# led_reflector.net
KiCad netlist of a schematic drawn in EAGLE
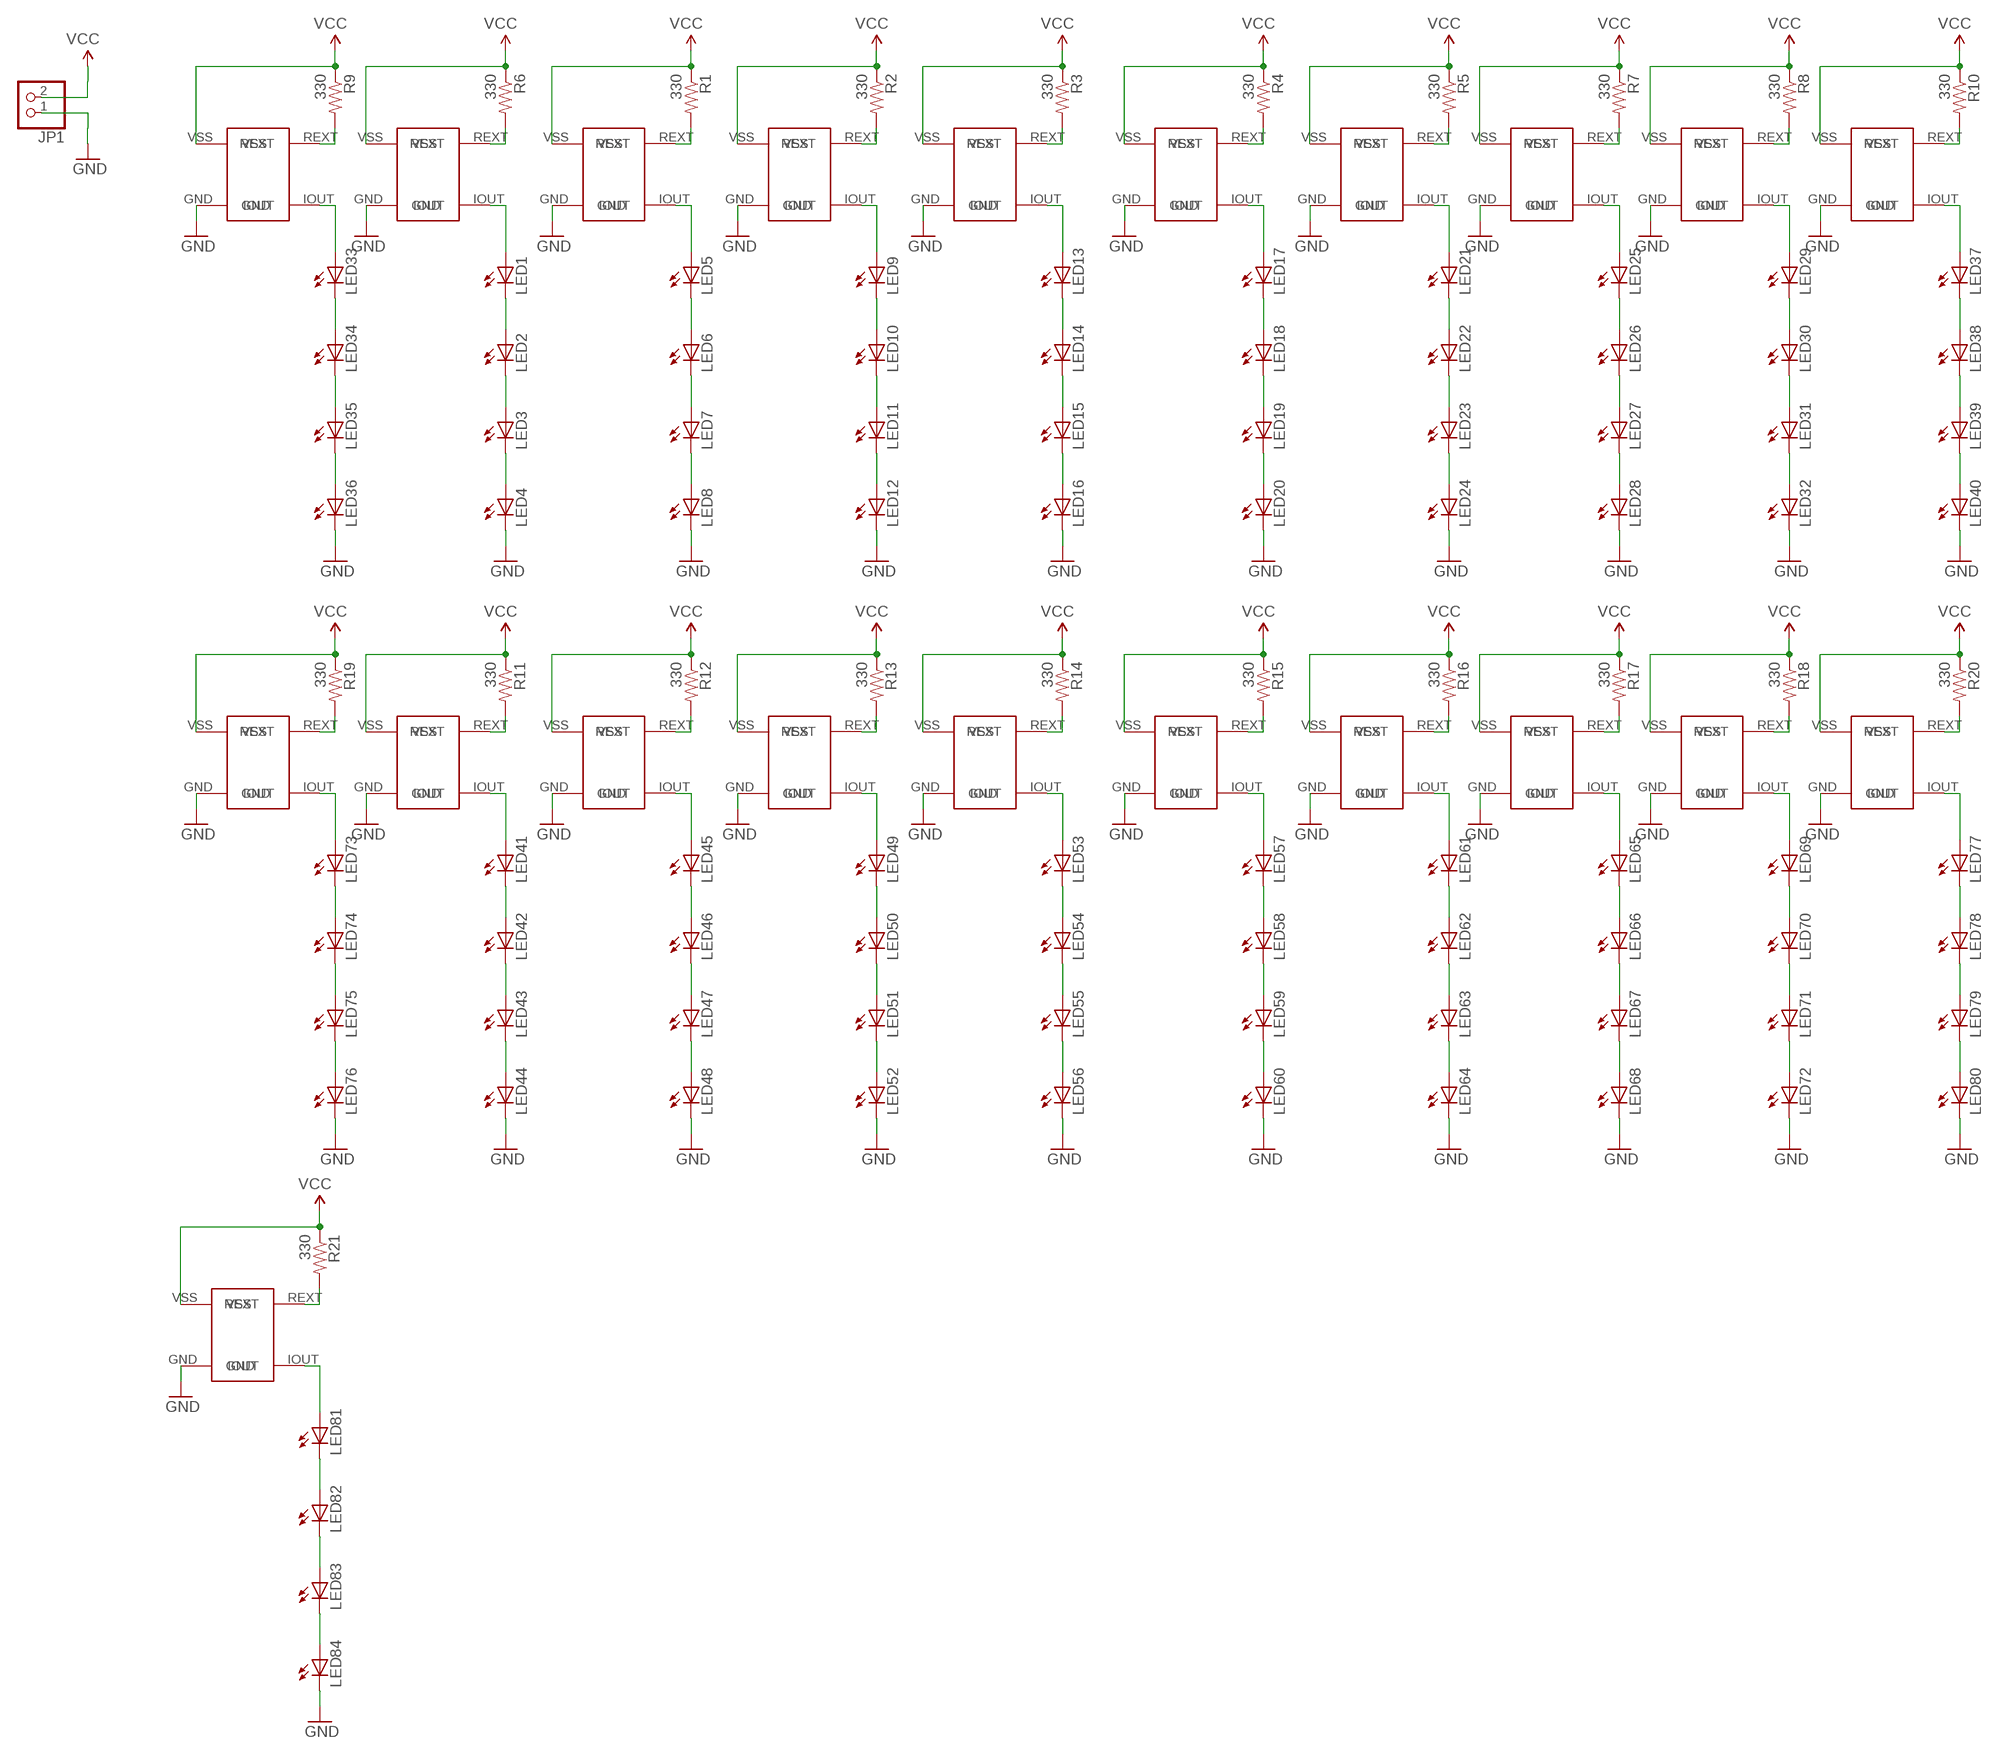
[diagram p0: schematic, sheet 1]

(export (version "E")
  (design (tool "Eeschema 10.0.6"))
  (components
    (comp (ref "JP1")
      (value "PINHD-1X2")
      (footprint "eagle-import:1X02")
      (libsource (lib "eagle-import") (part "PINHD-1X2"))
    )
    (comp (ref "LED1")
      (value "LED5MM")
      (footprint "eagle-import:LED5MM")
      (libsource (lib "eagle-import") (part "LED5MM"))
    )
    (comp (ref "LED2")
      (value "LED5MM")
      (footprint "eagle-import:LED5MM")
      (libsource (lib "eagle-import") (part "LED5MM"))
    )
    (comp (ref "LED3")
      (value "LED5MM")
      (footprint "eagle-import:LED5MM")
      (libsource (lib "eagle-import") (part "LED5MM"))
    )
    (comp (ref "LED4")
      (value "LED5MM")
      (footprint "eagle-import:LED5MM")
      (libsource (lib "eagle-import") (part "LED5MM"))
    )
    (comp (ref "LED5")
      (value "LED5MM")
      (footprint "eagle-import:LED5MM")
      (libsource (lib "eagle-import") (part "LED5MM"))
    )
    (comp (ref "LED6")
      (value "LED5MM")
      (footprint "eagle-import:LED5MM")
      (libsource (lib "eagle-import") (part "LED5MM"))
    )
    (comp (ref "LED7")
      (value "LED5MM")
      (footprint "eagle-import:LED5MM")
      (libsource (lib "eagle-import") (part "LED5MM"))
    )
    (comp (ref "LED8")
      (value "LED5MM")
      (footprint "eagle-import:LED5MM")
      (libsource (lib "eagle-import") (part "LED5MM"))
    )
    (comp (ref "LED9")
      (value "LED5MM")
      (footprint "eagle-import:LED5MM")
      (libsource (lib "eagle-import") (part "LED5MM"))
    )
    (comp (ref "LED10")
      (value "LED5MM")
      (footprint "eagle-import:LED5MM")
      (libsource (lib "eagle-import") (part "LED5MM"))
    )
    (comp (ref "LED11")
      (value "LED5MM")
      (footprint "eagle-import:LED5MM")
      (libsource (lib "eagle-import") (part "LED5MM"))
    )
    (comp (ref "LED12")
      (value "LED5MM")
      (footprint "eagle-import:LED5MM")
      (libsource (lib "eagle-import") (part "LED5MM"))
    )
    (comp (ref "LED13")
      (value "LED5MM")
      (footprint "eagle-import:LED5MM")
      (libsource (lib "eagle-import") (part "LED5MM"))
    )
    (comp (ref "LED14")
      (value "LED5MM")
      (footprint "eagle-import:LED5MM")
      (libsource (lib "eagle-import") (part "LED5MM"))
    )
    (comp (ref "LED15")
      (value "LED5MM")
      (footprint "eagle-import:LED5MM")
      (libsource (lib "eagle-import") (part "LED5MM"))
    )
    (comp (ref "LED16")
      (value "LED5MM")
      (footprint "eagle-import:LED5MM")
      (libsource (lib "eagle-import") (part "LED5MM"))
    )
    (comp (ref "LED17")
      (value "LED5MM")
      (footprint "eagle-import:LED5MM")
      (libsource (lib "eagle-import") (part "LED5MM"))
    )
    (comp (ref "LED18")
      (value "LED5MM")
      (footprint "eagle-import:LED5MM")
      (libsource (lib "eagle-import") (part "LED5MM"))
    )
    (comp (ref "LED19")
      (value "LED5MM")
      (footprint "eagle-import:LED5MM")
      (libsource (lib "eagle-import") (part "LED5MM"))
    )
    (comp (ref "LED20")
      (value "LED5MM")
      (footprint "eagle-import:LED5MM")
      (libsource (lib "eagle-import") (part "LED5MM"))
    )
    (comp (ref "LED21")
      (value "LED5MM")
      (footprint "eagle-import:LED5MM")
      (libsource (lib "eagle-import") (part "LED5MM"))
    )
    (comp (ref "LED22")
      (value "LED5MM")
      (footprint "eagle-import:LED5MM")
      (libsource (lib "eagle-import") (part "LED5MM"))
    )
    (comp (ref "LED23")
      (value "LED5MM")
      (footprint "eagle-import:LED5MM")
      (libsource (lib "eagle-import") (part "LED5MM"))
    )
    (comp (ref "LED24")
      (value "LED5MM")
      (footprint "eagle-import:LED5MM")
      (libsource (lib "eagle-import") (part "LED5MM"))
    )
    (comp (ref "LED25")
      (value "LED5MM")
      (footprint "eagle-import:LED5MM")
      (libsource (lib "eagle-import") (part "LED5MM"))
    )
    (comp (ref "LED26")
      (value "LED5MM")
      (footprint "eagle-import:LED5MM")
      (libsource (lib "eagle-import") (part "LED5MM"))
    )
    (comp (ref "LED27")
      (value "LED5MM")
      (footprint "eagle-import:LED5MM")
      (libsource (lib "eagle-import") (part "LED5MM"))
    )
    (comp (ref "LED28")
      (value "LED5MM")
      (footprint "eagle-import:LED5MM")
      (libsource (lib "eagle-import") (part "LED5MM"))
    )
    (comp (ref "LED29")
      (value "LED5MM")
      (footprint "eagle-import:LED5MM")
      (libsource (lib "eagle-import") (part "LED5MM"))
    )
    (comp (ref "LED30")
      (value "LED5MM")
      (footprint "eagle-import:LED5MM")
      (libsource (lib "eagle-import") (part "LED5MM"))
    )
    (comp (ref "LED31")
      (value "LED5MM")
      (footprint "eagle-import:LED5MM")
      (libsource (lib "eagle-import") (part "LED5MM"))
    )
    (comp (ref "LED32")
      (value "LED5MM")
      (footprint "eagle-import:LED5MM")
      (libsource (lib "eagle-import") (part "LED5MM"))
    )
    (comp (ref "LED33")
      (value "LED5MM")
      (footprint "eagle-import:LED5MM")
      (libsource (lib "eagle-import") (part "LED5MM"))
    )
    (comp (ref "LED34")
      (value "LED5MM")
      (footprint "eagle-import:LED5MM")
      (libsource (lib "eagle-import") (part "LED5MM"))
    )
    (comp (ref "LED35")
      (value "LED5MM")
      (footprint "eagle-import:LED5MM")
      (libsource (lib "eagle-import") (part "LED5MM"))
    )
    (comp (ref "LED36")
      (value "LED5MM")
      (footprint "eagle-import:LED5MM")
      (libsource (lib "eagle-import") (part "LED5MM"))
    )
    (comp (ref "LED37")
      (value "LED5MM")
      (footprint "eagle-import:LED5MM")
      (libsource (lib "eagle-import") (part "LED5MM"))
    )
    (comp (ref "LED38")
      (value "LED5MM")
      (footprint "eagle-import:LED5MM")
      (libsource (lib "eagle-import") (part "LED5MM"))
    )
    (comp (ref "LED39")
      (value "LED5MM")
      (footprint "eagle-import:LED5MM")
      (libsource (lib "eagle-import") (part "LED5MM"))
    )
    (comp (ref "LED40")
      (value "LED5MM")
      (footprint "eagle-import:LED5MM")
      (libsource (lib "eagle-import") (part "LED5MM"))
    )
    (comp (ref "LED41")
      (value "LED5MM")
      (footprint "eagle-import:LED5MM")
      (libsource (lib "eagle-import") (part "LED5MM"))
    )
    (comp (ref "LED42")
      (value "LED5MM")
      (footprint "eagle-import:LED5MM")
      (libsource (lib "eagle-import") (part "LED5MM"))
    )
    (comp (ref "LED43")
      (value "LED5MM")
      (footprint "eagle-import:LED5MM")
      (libsource (lib "eagle-import") (part "LED5MM"))
    )
    (comp (ref "LED44")
      (value "LED5MM")
      (footprint "eagle-import:LED5MM")
      (libsource (lib "eagle-import") (part "LED5MM"))
    )
    (comp (ref "LED45")
      (value "LED5MM")
      (footprint "eagle-import:LED5MM")
      (libsource (lib "eagle-import") (part "LED5MM"))
    )
    (comp (ref "LED46")
      (value "LED5MM")
      (footprint "eagle-import:LED5MM")
      (libsource (lib "eagle-import") (part "LED5MM"))
    )
    (comp (ref "LED47")
      (value "LED5MM")
      (footprint "eagle-import:LED5MM")
      (libsource (lib "eagle-import") (part "LED5MM"))
    )
    (comp (ref "LED48")
      (value "LED5MM")
      (footprint "eagle-import:LED5MM")
      (libsource (lib "eagle-import") (part "LED5MM"))
    )
    (comp (ref "LED49")
      (value "LED5MM")
      (footprint "eagle-import:LED5MM")
      (libsource (lib "eagle-import") (part "LED5MM"))
    )
    (comp (ref "LED50")
      (value "LED5MM")
      (footprint "eagle-import:LED5MM")
      (libsource (lib "eagle-import") (part "LED5MM"))
    )
    (comp (ref "LED51")
      (value "LED5MM")
      (footprint "eagle-import:LED5MM")
      (libsource (lib "eagle-import") (part "LED5MM"))
    )
    (comp (ref "LED52")
      (value "LED5MM")
      (footprint "eagle-import:LED5MM")
      (libsource (lib "eagle-import") (part "LED5MM"))
    )
    (comp (ref "LED53")
      (value "LED5MM")
      (footprint "eagle-import:LED5MM")
      (libsource (lib "eagle-import") (part "LED5MM"))
    )
    (comp (ref "LED54")
      (value "LED5MM")
      (footprint "eagle-import:LED5MM")
      (libsource (lib "eagle-import") (part "LED5MM"))
    )
    (comp (ref "LED55")
      (value "LED5MM")
      (footprint "eagle-import:LED5MM")
      (libsource (lib "eagle-import") (part "LED5MM"))
    )
    (comp (ref "LED56")
      (value "LED5MM")
      (footprint "eagle-import:LED5MM")
      (libsource (lib "eagle-import") (part "LED5MM"))
    )
    (comp (ref "LED57")
      (value "LED5MM")
      (footprint "eagle-import:LED5MM")
      (libsource (lib "eagle-import") (part "LED5MM"))
    )
    (comp (ref "LED58")
      (value "LED5MM")
      (footprint "eagle-import:LED5MM")
      (libsource (lib "eagle-import") (part "LED5MM"))
    )
    (comp (ref "LED59")
      (value "LED5MM")
      (footprint "eagle-import:LED5MM")
      (libsource (lib "eagle-import") (part "LED5MM"))
    )
    (comp (ref "LED60")
      (value "LED5MM")
      (footprint "eagle-import:LED5MM")
      (libsource (lib "eagle-import") (part "LED5MM"))
    )
    (comp (ref "LED61")
      (value "LED5MM")
      (footprint "eagle-import:LED5MM")
      (libsource (lib "eagle-import") (part "LED5MM"))
    )
    (comp (ref "LED62")
      (value "LED5MM")
      (footprint "eagle-import:LED5MM")
      (libsource (lib "eagle-import") (part "LED5MM"))
    )
    (comp (ref "LED63")
      (value "LED5MM")
      (footprint "eagle-import:LED5MM")
      (libsource (lib "eagle-import") (part "LED5MM"))
    )
    (comp (ref "LED64")
      (value "LED5MM")
      (footprint "eagle-import:LED5MM")
      (libsource (lib "eagle-import") (part "LED5MM"))
    )
    (comp (ref "LED65")
      (value "LED5MM")
      (footprint "eagle-import:LED5MM")
      (libsource (lib "eagle-import") (part "LED5MM"))
    )
    (comp (ref "LED66")
      (value "LED5MM")
      (footprint "eagle-import:LED5MM")
      (libsource (lib "eagle-import") (part "LED5MM"))
    )
    (comp (ref "LED67")
      (value "LED5MM")
      (footprint "eagle-import:LED5MM")
      (libsource (lib "eagle-import") (part "LED5MM"))
    )
    (comp (ref "LED68")
      (value "LED5MM")
      (footprint "eagle-import:LED5MM")
      (libsource (lib "eagle-import") (part "LED5MM"))
    )
    (comp (ref "LED69")
      (value "LED5MM")
      (footprint "eagle-import:LED5MM")
      (libsource (lib "eagle-import") (part "LED5MM"))
    )
    (comp (ref "LED70")
      (value "LED5MM")
      (footprint "eagle-import:LED5MM")
      (libsource (lib "eagle-import") (part "LED5MM"))
    )
    (comp (ref "LED71")
      (value "LED5MM")
      (footprint "eagle-import:LED5MM")
      (libsource (lib "eagle-import") (part "LED5MM"))
    )
    (comp (ref "LED72")
      (value "LED5MM")
      (footprint "eagle-import:LED5MM")
      (libsource (lib "eagle-import") (part "LED5MM"))
    )
    (comp (ref "LED73")
      (value "LED5MM")
      (footprint "eagle-import:LED5MM")
      (libsource (lib "eagle-import") (part "LED5MM"))
    )
    (comp (ref "LED74")
      (value "LED5MM")
      (footprint "eagle-import:LED5MM")
      (libsource (lib "eagle-import") (part "LED5MM"))
    )
    (comp (ref "LED75")
      (value "LED5MM")
      (footprint "eagle-import:LED5MM")
      (libsource (lib "eagle-import") (part "LED5MM"))
    )
    (comp (ref "LED76")
      (value "LED5MM")
      (footprint "eagle-import:LED5MM")
      (libsource (lib "eagle-import") (part "LED5MM"))
    )
    (comp (ref "LED77")
      (value "LED5MM")
      (footprint "eagle-import:LED5MM")
      (libsource (lib "eagle-import") (part "LED5MM"))
    )
    (comp (ref "LED78")
      (value "LED5MM")
      (footprint "eagle-import:LED5MM")
      (libsource (lib "eagle-import") (part "LED5MM"))
    )
    (comp (ref "LED79")
      (value "LED5MM")
      (footprint "eagle-import:LED5MM")
      (libsource (lib "eagle-import") (part "LED5MM"))
    )
    (comp (ref "LED80")
      (value "LED5MM")
      (footprint "eagle-import:LED5MM")
      (libsource (lib "eagle-import") (part "LED5MM"))
    )
    (comp (ref "LED81")
      (value "LED5MM")
      (footprint "eagle-import:LED5MM")
      (libsource (lib "eagle-import") (part "LED5MM"))
    )
    (comp (ref "LED82")
      (value "LED5MM")
      (footprint "eagle-import:LED5MM")
      (libsource (lib "eagle-import") (part "LED5MM"))
    )
    (comp (ref "LED83")
      (value "LED5MM")
      (footprint "eagle-import:LED5MM")
      (libsource (lib "eagle-import") (part "LED5MM"))
    )
    (comp (ref "LED84")
      (value "LED5MM")
      (footprint "eagle-import:LED5MM")
      (libsource (lib "eagle-import") (part "LED5MM"))
    )
    (comp (ref "R1")
      (value "330")
      (footprint "eagle-import:0805")
      (libsource (lib "eagle-import") (part "RESISTOR"))
    )
    (comp (ref "R2")
      (value "330")
      (footprint "eagle-import:0805")
      (libsource (lib "eagle-import") (part "RESISTOR"))
    )
    (comp (ref "R3")
      (value "330")
      (footprint "eagle-import:0805")
      (libsource (lib "eagle-import") (part "RESISTOR"))
    )
    (comp (ref "R4")
      (value "330")
      (footprint "eagle-import:0805")
      (libsource (lib "eagle-import") (part "RESISTOR"))
    )
    (comp (ref "R5")
      (value "330")
      (footprint "eagle-import:0805")
      (libsource (lib "eagle-import") (part "RESISTOR"))
    )
    (comp (ref "R6")
      (value "330")
      (footprint "eagle-import:0805")
      (libsource (lib "eagle-import") (part "RESISTOR"))
    )
    (comp (ref "R7")
      (value "330")
      (footprint "eagle-import:0805")
      (libsource (lib "eagle-import") (part "RESISTOR"))
    )
    (comp (ref "R8")
      (value "330")
      (footprint "eagle-import:0805")
      (libsource (lib "eagle-import") (part "RESISTOR"))
    )
    (comp (ref "R9")
      (value "330")
      (footprint "eagle-import:0805")
      (libsource (lib "eagle-import") (part "RESISTOR"))
    )
    (comp (ref "R10")
      (value "330")
      (footprint "eagle-import:0805")
      (libsource (lib "eagle-import") (part "RESISTOR"))
    )
    (comp (ref "R11")
      (value "330")
      (footprint "eagle-import:0805")
      (libsource (lib "eagle-import") (part "RESISTOR"))
    )
    (comp (ref "R12")
      (value "330")
      (footprint "eagle-import:0805")
      (libsource (lib "eagle-import") (part "RESISTOR"))
    )
    (comp (ref "R13")
      (value "330")
      (footprint "eagle-import:0805")
      (libsource (lib "eagle-import") (part "RESISTOR"))
    )
    (comp (ref "R14")
      (value "330")
      (footprint "eagle-import:0805")
      (libsource (lib "eagle-import") (part "RESISTOR"))
    )
    (comp (ref "R15")
      (value "330")
      (footprint "eagle-import:0805")
      (libsource (lib "eagle-import") (part "RESISTOR"))
    )
    (comp (ref "R16")
      (value "330")
      (footprint "eagle-import:0805")
      (libsource (lib "eagle-import") (part "RESISTOR"))
    )
    (comp (ref "R17")
      (value "330")
      (footprint "eagle-import:0805")
      (libsource (lib "eagle-import") (part "RESISTOR"))
    )
    (comp (ref "R18")
      (value "330")
      (footprint "eagle-import:0805")
      (libsource (lib "eagle-import") (part "RESISTOR"))
    )
    (comp (ref "R19")
      (value "330")
      (footprint "eagle-import:0805")
      (libsource (lib "eagle-import") (part "RESISTOR"))
    )
    (comp (ref "R20")
      (value "330")
      (footprint "eagle-import:0805")
      (libsource (lib "eagle-import") (part "RESISTOR"))
    )
    (comp (ref "R21")
      (value "330")
      (footprint "eagle-import:0805")
      (libsource (lib "eagle-import") (part "RESISTOR"))
    )
    (comp (ref "U$1")
      (value "BCR401W")
      (footprint "eagle-import:SOT-343")
      (libsource (lib "eagle-import") (part "BCR401W"))
    )
    (comp (ref "U$2")
      (value "BCR401W")
      (footprint "eagle-import:SOT-343")
      (libsource (lib "eagle-import") (part "BCR401W"))
    )
    (comp (ref "U$3")
      (value "BCR401W")
      (footprint "eagle-import:SOT-343")
      (libsource (lib "eagle-import") (part "BCR401W"))
    )
    (comp (ref "U$4")
      (value "BCR401W")
      (footprint "eagle-import:SOT-343")
      (libsource (lib "eagle-import") (part "BCR401W"))
    )
    (comp (ref "U$5")
      (value "BCR401W")
      (footprint "eagle-import:SOT-343")
      (libsource (lib "eagle-import") (part "BCR401W"))
    )
    (comp (ref "U$6")
      (value "BCR401W")
      (footprint "eagle-import:SOT-343")
      (libsource (lib "eagle-import") (part "BCR401W"))
    )
    (comp (ref "U$7")
      (value "BCR401W")
      (footprint "eagle-import:SOT-343")
      (libsource (lib "eagle-import") (part "BCR401W"))
    )
    (comp (ref "U$8")
      (value "BCR401W")
      (footprint "eagle-import:SOT-343")
      (libsource (lib "eagle-import") (part "BCR401W"))
    )
    (comp (ref "U$9")
      (value "BCR401W")
      (footprint "eagle-import:SOT-343")
      (libsource (lib "eagle-import") (part "BCR401W"))
    )
    (comp (ref "U$10")
      (value "BCR401W")
      (footprint "eagle-import:SOT-343")
      (libsource (lib "eagle-import") (part "BCR401W"))
    )
    (comp (ref "U$11")
      (value "BCR401W")
      (footprint "eagle-import:SOT-343")
      (libsource (lib "eagle-import") (part "BCR401W"))
    )
    (comp (ref "U$12")
      (value "BCR401W")
      (footprint "eagle-import:SOT-343")
      (libsource (lib "eagle-import") (part "BCR401W"))
    )
    (comp (ref "U$13")
      (value "BCR401W")
      (footprint "eagle-import:SOT-343")
      (libsource (lib "eagle-import") (part "BCR401W"))
    )
    (comp (ref "U$14")
      (value "BCR401W")
      (footprint "eagle-import:SOT-343")
      (libsource (lib "eagle-import") (part "BCR401W"))
    )
    (comp (ref "U$15")
      (value "BCR401W")
      (footprint "eagle-import:SOT-343")
      (libsource (lib "eagle-import") (part "BCR401W"))
    )
    (comp (ref "U$16")
      (value "BCR401W")
      (footprint "eagle-import:SOT-343")
      (libsource (lib "eagle-import") (part "BCR401W"))
    )
    (comp (ref "U$17")
      (value "BCR401W")
      (footprint "eagle-import:SOT-343")
      (libsource (lib "eagle-import") (part "BCR401W"))
    )
    (comp (ref "U$18")
      (value "BCR401W")
      (footprint "eagle-import:SOT-343")
      (libsource (lib "eagle-import") (part "BCR401W"))
    )
    (comp (ref "U$19")
      (value "BCR401W")
      (footprint "eagle-import:SOT-343")
      (libsource (lib "eagle-import") (part "BCR401W"))
    )
    (comp (ref "U$20")
      (value "BCR401W")
      (footprint "eagle-import:SOT-343")
      (libsource (lib "eagle-import") (part "BCR401W"))
    )
    (comp (ref "U$21")
      (value "BCR401W")
      (footprint "eagle-import:SOT-343")
      (libsource (lib "eagle-import") (part "BCR401W"))
    )
  )
  (nets
    (net (code "1") (name "GND") (class "Default")
      (node (ref "JP1") (pin "1") (pinfunction "1_1") (pintype "passive"))
      (node (ref "LED12") (pin "K") (pinfunction "C_K") (pintype "passive"))
      (node (ref "LED16") (pin "K") (pinfunction "C_K") (pintype "passive"))
      (node (ref "LED20") (pin "K") (pinfunction "C_K") (pintype "passive"))
      (node (ref "LED24") (pin "K") (pinfunction "C_K") (pintype "passive"))
      (node (ref "LED28") (pin "K") (pinfunction "C_K") (pintype "passive"))
      (node (ref "LED32") (pin "K") (pinfunction "C_K") (pintype "passive"))
      (node (ref "LED36") (pin "K") (pinfunction "C_K") (pintype "passive"))
      (node (ref "LED4") (pin "K") (pinfunction "C_K") (pintype "passive"))
      (node (ref "LED40") (pin "K") (pinfunction "C_K") (pintype "passive"))
      (node (ref "LED44") (pin "K") (pinfunction "C_K") (pintype "passive"))
      (node (ref "LED48") (pin "K") (pinfunction "C_K") (pintype "passive"))
      (node (ref "LED52") (pin "K") (pinfunction "C_K") (pintype "passive"))
      (node (ref "LED56") (pin "K") (pinfunction "C_K") (pintype "passive"))
      (node (ref "LED60") (pin "K") (pinfunction "C_K") (pintype "passive"))
      (node (ref "LED64") (pin "K") (pinfunction "C_K") (pintype "passive"))
      (node (ref "LED68") (pin "K") (pinfunction "C_K") (pintype "passive"))
      (node (ref "LED72") (pin "K") (pinfunction "C_K") (pintype "passive"))
      (node (ref "LED76") (pin "K") (pinfunction "C_K") (pintype "passive"))
      (node (ref "LED8") (pin "K") (pinfunction "C_K") (pintype "passive"))
      (node (ref "LED80") (pin "K") (pinfunction "C_K") (pintype "passive"))
      (node (ref "LED84") (pin "K") (pinfunction "C_K") (pintype "passive"))
      (node (ref "U$1") (pin "GND") (pinfunction "GND_GND") (pintype "bidirectional"))
      (node (ref "U$10") (pin "GND") (pinfunction "GND_GND") (pintype "bidirectional"))
      (node (ref "U$11") (pin "GND") (pinfunction "GND_GND") (pintype "bidirectional"))
      (node (ref "U$12") (pin "GND") (pinfunction "GND_GND") (pintype "bidirectional"))
      (node (ref "U$13") (pin "GND") (pinfunction "GND_GND") (pintype "bidirectional"))
      (node (ref "U$14") (pin "GND") (pinfunction "GND_GND") (pintype "bidirectional"))
      (node (ref "U$15") (pin "GND") (pinfunction "GND_GND") (pintype "bidirectional"))
      (node (ref "U$16") (pin "GND") (pinfunction "GND_GND") (pintype "bidirectional"))
      (node (ref "U$17") (pin "GND") (pinfunction "GND_GND") (pintype "bidirectional"))
      (node (ref "U$18") (pin "GND") (pinfunction "GND_GND") (pintype "bidirectional"))
      (node (ref "U$19") (pin "GND") (pinfunction "GND_GND") (pintype "bidirectional"))
      (node (ref "U$2") (pin "GND") (pinfunction "GND_GND") (pintype "bidirectional"))
      (node (ref "U$20") (pin "GND") (pinfunction "GND_GND") (pintype "bidirectional"))
      (node (ref "U$21") (pin "GND") (pinfunction "GND_GND") (pintype "bidirectional"))
      (node (ref "U$3") (pin "GND") (pinfunction "GND_GND") (pintype "bidirectional"))
      (node (ref "U$4") (pin "GND") (pinfunction "GND_GND") (pintype "bidirectional"))
      (node (ref "U$5") (pin "GND") (pinfunction "GND_GND") (pintype "bidirectional"))
      (node (ref "U$6") (pin "GND") (pinfunction "GND_GND") (pintype "bidirectional"))
      (node (ref "U$7") (pin "GND") (pinfunction "GND_GND") (pintype "bidirectional"))
      (node (ref "U$8") (pin "GND") (pinfunction "GND_GND") (pintype "bidirectional"))
      (node (ref "U$9") (pin "GND") (pinfunction "GND_GND") (pintype "bidirectional"))
    )
    (net (code "2") (name "Net-(LED1-C)") (class "Default")
      (node (ref "LED1") (pin "K") (pinfunction "C_K") (pintype "passive"))
      (node (ref "LED2") (pin "A") (pinfunction "A_A") (pintype "passive"))
    )
    (net (code "3") (name "Net-(LED1-PadA)") (class "Default")
      (node (ref "LED1") (pin "A") (pinfunction "A_A") (pintype "passive"))
      (node (ref "U$1") (pin "IOUT") (pinfunction "IOUT_IOUT") (pintype "bidirectional"))
    )
    (net (code "4") (name "Net-(LED2-C)") (class "Default")
      (node (ref "LED2") (pin "K") (pinfunction "C_K") (pintype "passive"))
      (node (ref "LED3") (pin "A") (pinfunction "A_A") (pintype "passive"))
    )
    (net (code "5") (name "Net-(LED3-C)") (class "Default")
      (node (ref "LED3") (pin "K") (pinfunction "C_K") (pintype "passive"))
      (node (ref "LED4") (pin "A") (pinfunction "A_A") (pintype "passive"))
    )
    (net (code "6") (name "Net-(LED5-C)") (class "Default")
      (node (ref "LED5") (pin "K") (pinfunction "C_K") (pintype "passive"))
      (node (ref "LED6") (pin "A") (pinfunction "A_A") (pintype "passive"))
    )
    (net (code "7") (name "Net-(LED5-PadA)") (class "Default")
      (node (ref "LED5") (pin "A") (pinfunction "A_A") (pintype "passive"))
      (node (ref "U$2") (pin "IOUT") (pinfunction "IOUT_IOUT") (pintype "bidirectional"))
    )
    (net (code "8") (name "Net-(LED6-C)") (class "Default")
      (node (ref "LED6") (pin "K") (pinfunction "C_K") (pintype "passive"))
      (node (ref "LED7") (pin "A") (pinfunction "A_A") (pintype "passive"))
    )
    (net (code "9") (name "Net-(LED7-C)") (class "Default")
      (node (ref "LED7") (pin "K") (pinfunction "C_K") (pintype "passive"))
      (node (ref "LED8") (pin "A") (pinfunction "A_A") (pintype "passive"))
    )
    (net (code "10") (name "Net-(LED9-C)") (class "Default")
      (node (ref "LED10") (pin "A") (pinfunction "A_A") (pintype "passive"))
      (node (ref "LED9") (pin "K") (pinfunction "C_K") (pintype "passive"))
    )
    (net (code "11") (name "Net-(LED9-PadA)") (class "Default")
      (node (ref "LED9") (pin "A") (pinfunction "A_A") (pintype "passive"))
      (node (ref "U$3") (pin "IOUT") (pinfunction "IOUT_IOUT") (pintype "bidirectional"))
    )
    (net (code "12") (name "Net-(LED10-C)") (class "Default")
      (node (ref "LED10") (pin "K") (pinfunction "C_K") (pintype "passive"))
      (node (ref "LED11") (pin "A") (pinfunction "A_A") (pintype "passive"))
    )
    (net (code "13") (name "Net-(LED11-C)") (class "Default")
      (node (ref "LED11") (pin "K") (pinfunction "C_K") (pintype "passive"))
      (node (ref "LED12") (pin "A") (pinfunction "A_A") (pintype "passive"))
    )
    (net (code "14") (name "Net-(LED13-C)") (class "Default")
      (node (ref "LED13") (pin "K") (pinfunction "C_K") (pintype "passive"))
      (node (ref "LED14") (pin "A") (pinfunction "A_A") (pintype "passive"))
    )
    (net (code "15") (name "Net-(LED13-PadA)") (class "Default")
      (node (ref "LED13") (pin "A") (pinfunction "A_A") (pintype "passive"))
      (node (ref "U$4") (pin "IOUT") (pinfunction "IOUT_IOUT") (pintype "bidirectional"))
    )
    (net (code "16") (name "Net-(LED14-C)") (class "Default")
      (node (ref "LED14") (pin "K") (pinfunction "C_K") (pintype "passive"))
      (node (ref "LED15") (pin "A") (pinfunction "A_A") (pintype "passive"))
    )
    (net (code "17") (name "Net-(LED15-C)") (class "Default")
      (node (ref "LED15") (pin "K") (pinfunction "C_K") (pintype "passive"))
      (node (ref "LED16") (pin "A") (pinfunction "A_A") (pintype "passive"))
    )
    (net (code "18") (name "Net-(LED17-C)") (class "Default")
      (node (ref "LED17") (pin "K") (pinfunction "C_K") (pintype "passive"))
      (node (ref "LED18") (pin "A") (pinfunction "A_A") (pintype "passive"))
    )
    (net (code "19") (name "Net-(LED17-PadA)") (class "Default")
      (node (ref "LED17") (pin "A") (pinfunction "A_A") (pintype "passive"))
      (node (ref "U$5") (pin "IOUT") (pinfunction "IOUT_IOUT") (pintype "bidirectional"))
    )
    (net (code "20") (name "Net-(LED18-C)") (class "Default")
      (node (ref "LED18") (pin "K") (pinfunction "C_K") (pintype "passive"))
      (node (ref "LED19") (pin "A") (pinfunction "A_A") (pintype "passive"))
    )
    (net (code "21") (name "Net-(LED19-C)") (class "Default")
      (node (ref "LED19") (pin "K") (pinfunction "C_K") (pintype "passive"))
      (node (ref "LED20") (pin "A") (pinfunction "A_A") (pintype "passive"))
    )
    (net (code "22") (name "Net-(LED21-C)") (class "Default")
      (node (ref "LED21") (pin "K") (pinfunction "C_K") (pintype "passive"))
      (node (ref "LED22") (pin "A") (pinfunction "A_A") (pintype "passive"))
    )
    (net (code "23") (name "Net-(LED21-PadA)") (class "Default")
      (node (ref "LED21") (pin "A") (pinfunction "A_A") (pintype "passive"))
      (node (ref "U$6") (pin "IOUT") (pinfunction "IOUT_IOUT") (pintype "bidirectional"))
    )
    (net (code "24") (name "Net-(LED22-C)") (class "Default")
      (node (ref "LED22") (pin "K") (pinfunction "C_K") (pintype "passive"))
      (node (ref "LED23") (pin "A") (pinfunction "A_A") (pintype "passive"))
    )
    (net (code "25") (name "Net-(LED23-C)") (class "Default")
      (node (ref "LED23") (pin "K") (pinfunction "C_K") (pintype "passive"))
      (node (ref "LED24") (pin "A") (pinfunction "A_A") (pintype "passive"))
    )
    (net (code "26") (name "Net-(LED25-C)") (class "Default")
      (node (ref "LED25") (pin "K") (pinfunction "C_K") (pintype "passive"))
      (node (ref "LED26") (pin "A") (pinfunction "A_A") (pintype "passive"))
    )
    (net (code "27") (name "Net-(LED25-PadA)") (class "Default")
      (node (ref "LED25") (pin "A") (pinfunction "A_A") (pintype "passive"))
      (node (ref "U$7") (pin "IOUT") (pinfunction "IOUT_IOUT") (pintype "bidirectional"))
    )
    (net (code "28") (name "Net-(LED26-C)") (class "Default")
      (node (ref "LED26") (pin "K") (pinfunction "C_K") (pintype "passive"))
      (node (ref "LED27") (pin "A") (pinfunction "A_A") (pintype "passive"))
    )
    (net (code "29") (name "Net-(LED27-C)") (class "Default")
      (node (ref "LED27") (pin "K") (pinfunction "C_K") (pintype "passive"))
      (node (ref "LED28") (pin "A") (pinfunction "A_A") (pintype "passive"))
    )
    (net (code "30") (name "Net-(LED29-C)") (class "Default")
      (node (ref "LED29") (pin "K") (pinfunction "C_K") (pintype "passive"))
      (node (ref "LED30") (pin "A") (pinfunction "A_A") (pintype "passive"))
    )
    (net (code "31") (name "Net-(LED29-PadA)") (class "Default")
      (node (ref "LED29") (pin "A") (pinfunction "A_A") (pintype "passive"))
      (node (ref "U$8") (pin "IOUT") (pinfunction "IOUT_IOUT") (pintype "bidirectional"))
    )
    (net (code "32") (name "Net-(LED30-C)") (class "Default")
      (node (ref "LED30") (pin "K") (pinfunction "C_K") (pintype "passive"))
      (node (ref "LED31") (pin "A") (pinfunction "A_A") (pintype "passive"))
    )
    (net (code "33") (name "Net-(LED31-C)") (class "Default")
      (node (ref "LED31") (pin "K") (pinfunction "C_K") (pintype "passive"))
      (node (ref "LED32") (pin "A") (pinfunction "A_A") (pintype "passive"))
    )
    (net (code "34") (name "Net-(LED33-C)") (class "Default")
      (node (ref "LED33") (pin "K") (pinfunction "C_K") (pintype "passive"))
      (node (ref "LED34") (pin "A") (pinfunction "A_A") (pintype "passive"))
    )
    (net (code "35") (name "Net-(LED33-PadA)") (class "Default")
      (node (ref "LED33") (pin "A") (pinfunction "A_A") (pintype "passive"))
      (node (ref "U$9") (pin "IOUT") (pinfunction "IOUT_IOUT") (pintype "bidirectional"))
    )
    (net (code "36") (name "Net-(LED34-C)") (class "Default")
      (node (ref "LED34") (pin "K") (pinfunction "C_K") (pintype "passive"))
      (node (ref "LED35") (pin "A") (pinfunction "A_A") (pintype "passive"))
    )
    (net (code "37") (name "Net-(LED35-C)") (class "Default")
      (node (ref "LED35") (pin "K") (pinfunction "C_K") (pintype "passive"))
      (node (ref "LED36") (pin "A") (pinfunction "A_A") (pintype "passive"))
    )
    (net (code "38") (name "Net-(LED37-C)") (class "Default")
      (node (ref "LED37") (pin "K") (pinfunction "C_K") (pintype "passive"))
      (node (ref "LED38") (pin "A") (pinfunction "A_A") (pintype "passive"))
    )
    (net (code "39") (name "Net-(LED37-PadA)") (class "Default")
      (node (ref "LED37") (pin "A") (pinfunction "A_A") (pintype "passive"))
      (node (ref "U$10") (pin "IOUT") (pinfunction "IOUT_IOUT") (pintype "bidirectional"))
    )
    (net (code "40") (name "Net-(LED38-C)") (class "Default")
      (node (ref "LED38") (pin "K") (pinfunction "C_K") (pintype "passive"))
      (node (ref "LED39") (pin "A") (pinfunction "A_A") (pintype "passive"))
    )
    (net (code "41") (name "Net-(LED39-C)") (class "Default")
      (node (ref "LED39") (pin "K") (pinfunction "C_K") (pintype "passive"))
      (node (ref "LED40") (pin "A") (pinfunction "A_A") (pintype "passive"))
    )
    (net (code "42") (name "Net-(LED41-C)") (class "Default")
      (node (ref "LED41") (pin "K") (pinfunction "C_K") (pintype "passive"))
      (node (ref "LED42") (pin "A") (pinfunction "A_A") (pintype "passive"))
    )
    (net (code "43") (name "Net-(LED41-PadA)") (class "Default")
      (node (ref "LED41") (pin "A") (pinfunction "A_A") (pintype "passive"))
      (node (ref "U$11") (pin "IOUT") (pinfunction "IOUT_IOUT") (pintype "bidirectional"))
    )
    (net (code "44") (name "Net-(LED42-C)") (class "Default")
      (node (ref "LED42") (pin "K") (pinfunction "C_K") (pintype "passive"))
      (node (ref "LED43") (pin "A") (pinfunction "A_A") (pintype "passive"))
    )
    (net (code "45") (name "Net-(LED43-C)") (class "Default")
      (node (ref "LED43") (pin "K") (pinfunction "C_K") (pintype "passive"))
      (node (ref "LED44") (pin "A") (pinfunction "A_A") (pintype "passive"))
    )
    (net (code "46") (name "Net-(LED45-C)") (class "Default")
      (node (ref "LED45") (pin "K") (pinfunction "C_K") (pintype "passive"))
      (node (ref "LED46") (pin "A") (pinfunction "A_A") (pintype "passive"))
    )
    (net (code "47") (name "Net-(LED45-PadA)") (class "Default")
      (node (ref "LED45") (pin "A") (pinfunction "A_A") (pintype "passive"))
      (node (ref "U$12") (pin "IOUT") (pinfunction "IOUT_IOUT") (pintype "bidirectional"))
    )
    (net (code "48") (name "Net-(LED46-C)") (class "Default")
      (node (ref "LED46") (pin "K") (pinfunction "C_K") (pintype "passive"))
      (node (ref "LED47") (pin "A") (pinfunction "A_A") (pintype "passive"))
    )
    (net (code "49") (name "Net-(LED47-C)") (class "Default")
      (node (ref "LED47") (pin "K") (pinfunction "C_K") (pintype "passive"))
      (node (ref "LED48") (pin "A") (pinfunction "A_A") (pintype "passive"))
    )
    (net (code "50") (name "Net-(LED49-C)") (class "Default")
      (node (ref "LED49") (pin "K") (pinfunction "C_K") (pintype "passive"))
      (node (ref "LED50") (pin "A") (pinfunction "A_A") (pintype "passive"))
    )
    (net (code "51") (name "Net-(LED49-PadA)") (class "Default")
      (node (ref "LED49") (pin "A") (pinfunction "A_A") (pintype "passive"))
      (node (ref "U$13") (pin "IOUT") (pinfunction "IOUT_IOUT") (pintype "bidirectional"))
    )
    (net (code "52") (name "Net-(LED50-C)") (class "Default")
      (node (ref "LED50") (pin "K") (pinfunction "C_K") (pintype "passive"))
      (node (ref "LED51") (pin "A") (pinfunction "A_A") (pintype "passive"))
    )
    (net (code "53") (name "Net-(LED51-C)") (class "Default")
      (node (ref "LED51") (pin "K") (pinfunction "C_K") (pintype "passive"))
      (node (ref "LED52") (pin "A") (pinfunction "A_A") (pintype "passive"))
    )
    (net (code "54") (name "Net-(LED53-C)") (class "Default")
      (node (ref "LED53") (pin "K") (pinfunction "C_K") (pintype "passive"))
      (node (ref "LED54") (pin "A") (pinfunction "A_A") (pintype "passive"))
    )
    (net (code "55") (name "Net-(LED53-PadA)") (class "Default")
      (node (ref "LED53") (pin "A") (pinfunction "A_A") (pintype "passive"))
      (node (ref "U$14") (pin "IOUT") (pinfunction "IOUT_IOUT") (pintype "bidirectional"))
    )
    (net (code "56") (name "Net-(LED54-C)") (class "Default")
      (node (ref "LED54") (pin "K") (pinfunction "C_K") (pintype "passive"))
      (node (ref "LED55") (pin "A") (pinfunction "A_A") (pintype "passive"))
    )
    (net (code "57") (name "Net-(LED55-C)") (class "Default")
      (node (ref "LED55") (pin "K") (pinfunction "C_K") (pintype "passive"))
      (node (ref "LED56") (pin "A") (pinfunction "A_A") (pintype "passive"))
    )
    (net (code "58") (name "Net-(LED57-C)") (class "Default")
      (node (ref "LED57") (pin "K") (pinfunction "C_K") (pintype "passive"))
      (node (ref "LED58") (pin "A") (pinfunction "A_A") (pintype "passive"))
    )
    (net (code "59") (name "Net-(LED57-PadA)") (class "Default")
      (node (ref "LED57") (pin "A") (pinfunction "A_A") (pintype "passive"))
      (node (ref "U$15") (pin "IOUT") (pinfunction "IOUT_IOUT") (pintype "bidirectional"))
    )
    (net (code "60") (name "Net-(LED58-C)") (class "Default")
      (node (ref "LED58") (pin "K") (pinfunction "C_K") (pintype "passive"))
      (node (ref "LED59") (pin "A") (pinfunction "A_A") (pintype "passive"))
    )
    (net (code "61") (name "Net-(LED59-C)") (class "Default")
      (node (ref "LED59") (pin "K") (pinfunction "C_K") (pintype "passive"))
      (node (ref "LED60") (pin "A") (pinfunction "A_A") (pintype "passive"))
    )
    (net (code "62") (name "Net-(LED61-C)") (class "Default")
      (node (ref "LED61") (pin "K") (pinfunction "C_K") (pintype "passive"))
      (node (ref "LED62") (pin "A") (pinfunction "A_A") (pintype "passive"))
    )
    (net (code "63") (name "Net-(LED61-PadA)") (class "Default")
      (node (ref "LED61") (pin "A") (pinfunction "A_A") (pintype "passive"))
      (node (ref "U$16") (pin "IOUT") (pinfunction "IOUT_IOUT") (pintype "bidirectional"))
    )
    (net (code "64") (name "Net-(LED62-C)") (class "Default")
      (node (ref "LED62") (pin "K") (pinfunction "C_K") (pintype "passive"))
      (node (ref "LED63") (pin "A") (pinfunction "A_A") (pintype "passive"))
    )
    (net (code "65") (name "Net-(LED63-C)") (class "Default")
      (node (ref "LED63") (pin "K") (pinfunction "C_K") (pintype "passive"))
      (node (ref "LED64") (pin "A") (pinfunction "A_A") (pintype "passive"))
    )
    (net (code "66") (name "Net-(LED65-C)") (class "Default")
      (node (ref "LED65") (pin "K") (pinfunction "C_K") (pintype "passive"))
      (node (ref "LED66") (pin "A") (pinfunction "A_A") (pintype "passive"))
    )
    (net (code "67") (name "Net-(LED65-PadA)") (class "Default")
      (node (ref "LED65") (pin "A") (pinfunction "A_A") (pintype "passive"))
      (node (ref "U$17") (pin "IOUT") (pinfunction "IOUT_IOUT") (pintype "bidirectional"))
    )
    (net (code "68") (name "Net-(LED66-C)") (class "Default")
      (node (ref "LED66") (pin "K") (pinfunction "C_K") (pintype "passive"))
      (node (ref "LED67") (pin "A") (pinfunction "A_A") (pintype "passive"))
    )
    (net (code "69") (name "Net-(LED67-C)") (class "Default")
      (node (ref "LED67") (pin "K") (pinfunction "C_K") (pintype "passive"))
      (node (ref "LED68") (pin "A") (pinfunction "A_A") (pintype "passive"))
    )
    (net (code "70") (name "Net-(LED69-C)") (class "Default")
      (node (ref "LED69") (pin "K") (pinfunction "C_K") (pintype "passive"))
      (node (ref "LED70") (pin "A") (pinfunction "A_A") (pintype "passive"))
    )
    (net (code "71") (name "Net-(LED69-PadA)") (class "Default")
      (node (ref "LED69") (pin "A") (pinfunction "A_A") (pintype "passive"))
      (node (ref "U$18") (pin "IOUT") (pinfunction "IOUT_IOUT") (pintype "bidirectional"))
    )
    (net (code "72") (name "Net-(LED70-C)") (class "Default")
      (node (ref "LED70") (pin "K") (pinfunction "C_K") (pintype "passive"))
      (node (ref "LED71") (pin "A") (pinfunction "A_A") (pintype "passive"))
    )
    (net (code "73") (name "Net-(LED71-C)") (class "Default")
      (node (ref "LED71") (pin "K") (pinfunction "C_K") (pintype "passive"))
      (node (ref "LED72") (pin "A") (pinfunction "A_A") (pintype "passive"))
    )
    (net (code "74") (name "Net-(LED73-C)") (class "Default")
      (node (ref "LED73") (pin "K") (pinfunction "C_K") (pintype "passive"))
      (node (ref "LED74") (pin "A") (pinfunction "A_A") (pintype "passive"))
    )
    (net (code "75") (name "Net-(LED73-PadA)") (class "Default")
      (node (ref "LED73") (pin "A") (pinfunction "A_A") (pintype "passive"))
      (node (ref "U$19") (pin "IOUT") (pinfunction "IOUT_IOUT") (pintype "bidirectional"))
    )
    (net (code "76") (name "Net-(LED74-C)") (class "Default")
      (node (ref "LED74") (pin "K") (pinfunction "C_K") (pintype "passive"))
      (node (ref "LED75") (pin "A") (pinfunction "A_A") (pintype "passive"))
    )
    (net (code "77") (name "Net-(LED75-C)") (class "Default")
      (node (ref "LED75") (pin "K") (pinfunction "C_K") (pintype "passive"))
      (node (ref "LED76") (pin "A") (pinfunction "A_A") (pintype "passive"))
    )
    (net (code "78") (name "Net-(LED77-C)") (class "Default")
      (node (ref "LED77") (pin "K") (pinfunction "C_K") (pintype "passive"))
      (node (ref "LED78") (pin "A") (pinfunction "A_A") (pintype "passive"))
    )
    (net (code "79") (name "Net-(LED77-PadA)") (class "Default")
      (node (ref "LED77") (pin "A") (pinfunction "A_A") (pintype "passive"))
      (node (ref "U$20") (pin "IOUT") (pinfunction "IOUT_IOUT") (pintype "bidirectional"))
    )
    (net (code "80") (name "Net-(LED78-C)") (class "Default")
      (node (ref "LED78") (pin "K") (pinfunction "C_K") (pintype "passive"))
      (node (ref "LED79") (pin "A") (pinfunction "A_A") (pintype "passive"))
    )
    (net (code "81") (name "Net-(LED79-C)") (class "Default")
      (node (ref "LED79") (pin "K") (pinfunction "C_K") (pintype "passive"))
      (node (ref "LED80") (pin "A") (pinfunction "A_A") (pintype "passive"))
    )
    (net (code "82") (name "Net-(LED81-C)") (class "Default")
      (node (ref "LED81") (pin "K") (pinfunction "C_K") (pintype "passive"))
      (node (ref "LED82") (pin "A") (pinfunction "A_A") (pintype "passive"))
    )
    (net (code "83") (name "Net-(LED81-PadA)") (class "Default")
      (node (ref "LED81") (pin "A") (pinfunction "A_A") (pintype "passive"))
      (node (ref "U$21") (pin "IOUT") (pinfunction "IOUT_IOUT") (pintype "bidirectional"))
    )
    (net (code "84") (name "Net-(LED82-C)") (class "Default")
      (node (ref "LED82") (pin "K") (pinfunction "C_K") (pintype "passive"))
      (node (ref "LED83") (pin "A") (pinfunction "A_A") (pintype "passive"))
    )
    (net (code "85") (name "Net-(LED83-C)") (class "Default")
      (node (ref "LED83") (pin "K") (pinfunction "C_K") (pintype "passive"))
      (node (ref "LED84") (pin "A") (pinfunction "A_A") (pintype "passive"))
    )
    (net (code "86") (name "Net-(R1-Pad2)") (class "Default")
      (node (ref "R1") (pin "2") (pinfunction "2_2") (pintype "passive"))
      (node (ref "U$2") (pin "REXT") (pinfunction "REXT_REXT") (pintype "bidirectional"))
    )
    (net (code "87") (name "Net-(R2-Pad2)") (class "Default")
      (node (ref "R2") (pin "2") (pinfunction "2_2") (pintype "passive"))
      (node (ref "U$3") (pin "REXT") (pinfunction "REXT_REXT") (pintype "bidirectional"))
    )
    (net (code "88") (name "Net-(R3-Pad2)") (class "Default")
      (node (ref "R3") (pin "2") (pinfunction "2_2") (pintype "passive"))
      (node (ref "U$4") (pin "REXT") (pinfunction "REXT_REXT") (pintype "bidirectional"))
    )
    (net (code "89") (name "Net-(R4-Pad2)") (class "Default")
      (node (ref "R4") (pin "2") (pinfunction "2_2") (pintype "passive"))
      (node (ref "U$5") (pin "REXT") (pinfunction "REXT_REXT") (pintype "bidirectional"))
    )
    (net (code "90") (name "Net-(R5-Pad2)") (class "Default")
      (node (ref "R5") (pin "2") (pinfunction "2_2") (pintype "passive"))
      (node (ref "U$6") (pin "REXT") (pinfunction "REXT_REXT") (pintype "bidirectional"))
    )
    (net (code "91") (name "Net-(R6-Pad2)") (class "Default")
      (node (ref "R6") (pin "2") (pinfunction "2_2") (pintype "passive"))
      (node (ref "U$1") (pin "REXT") (pinfunction "REXT_REXT") (pintype "bidirectional"))
    )
    (net (code "92") (name "Net-(R7-Pad2)") (class "Default")
      (node (ref "R7") (pin "2") (pinfunction "2_2") (pintype "passive"))
      (node (ref "U$7") (pin "REXT") (pinfunction "REXT_REXT") (pintype "bidirectional"))
    )
    (net (code "93") (name "Net-(R8-Pad2)") (class "Default")
      (node (ref "R8") (pin "2") (pinfunction "2_2") (pintype "passive"))
      (node (ref "U$8") (pin "REXT") (pinfunction "REXT_REXT") (pintype "bidirectional"))
    )
    (net (code "94") (name "Net-(R9-Pad2)") (class "Default")
      (node (ref "R9") (pin "2") (pinfunction "2_2") (pintype "passive"))
      (node (ref "U$9") (pin "REXT") (pinfunction "REXT_REXT") (pintype "bidirectional"))
    )
    (net (code "95") (name "Net-(R10-Pad2)") (class "Default")
      (node (ref "R10") (pin "2") (pinfunction "2_2") (pintype "passive"))
      (node (ref "U$10") (pin "REXT") (pinfunction "REXT_REXT") (pintype "bidirectional"))
    )
    (net (code "96") (name "Net-(R11-Pad2)") (class "Default")
      (node (ref "R11") (pin "2") (pinfunction "2_2") (pintype "passive"))
      (node (ref "U$11") (pin "REXT") (pinfunction "REXT_REXT") (pintype "bidirectional"))
    )
    (net (code "97") (name "Net-(R12-Pad2)") (class "Default")
      (node (ref "R12") (pin "2") (pinfunction "2_2") (pintype "passive"))
      (node (ref "U$12") (pin "REXT") (pinfunction "REXT_REXT") (pintype "bidirectional"))
    )
    (net (code "98") (name "Net-(R13-Pad2)") (class "Default")
      (node (ref "R13") (pin "2") (pinfunction "2_2") (pintype "passive"))
      (node (ref "U$13") (pin "REXT") (pinfunction "REXT_REXT") (pintype "bidirectional"))
    )
    (net (code "99") (name "Net-(R14-Pad2)") (class "Default")
      (node (ref "R14") (pin "2") (pinfunction "2_2") (pintype "passive"))
      (node (ref "U$14") (pin "REXT") (pinfunction "REXT_REXT") (pintype "bidirectional"))
    )
    (net (code "100") (name "Net-(R15-Pad2)") (class "Default")
      (node (ref "R15") (pin "2") (pinfunction "2_2") (pintype "passive"))
      (node (ref "U$15") (pin "REXT") (pinfunction "REXT_REXT") (pintype "bidirectional"))
    )
    (net (code "101") (name "Net-(R16-Pad2)") (class "Default")
      (node (ref "R16") (pin "2") (pinfunction "2_2") (pintype "passive"))
      (node (ref "U$16") (pin "REXT") (pinfunction "REXT_REXT") (pintype "bidirectional"))
    )
    (net (code "102") (name "Net-(R17-Pad2)") (class "Default")
      (node (ref "R17") (pin "2") (pinfunction "2_2") (pintype "passive"))
      (node (ref "U$17") (pin "REXT") (pinfunction "REXT_REXT") (pintype "bidirectional"))
    )
    (net (code "103") (name "Net-(R18-Pad2)") (class "Default")
      (node (ref "R18") (pin "2") (pinfunction "2_2") (pintype "passive"))
      (node (ref "U$18") (pin "REXT") (pinfunction "REXT_REXT") (pintype "bidirectional"))
    )
    (net (code "104") (name "Net-(R19-Pad2)") (class "Default")
      (node (ref "R19") (pin "2") (pinfunction "2_2") (pintype "passive"))
      (node (ref "U$19") (pin "REXT") (pinfunction "REXT_REXT") (pintype "bidirectional"))
    )
    (net (code "105") (name "Net-(R20-Pad2)") (class "Default")
      (node (ref "R20") (pin "2") (pinfunction "2_2") (pintype "passive"))
      (node (ref "U$20") (pin "REXT") (pinfunction "REXT_REXT") (pintype "bidirectional"))
    )
    (net (code "106") (name "Net-(R21-Pad2)") (class "Default")
      (node (ref "R21") (pin "2") (pinfunction "2_2") (pintype "passive"))
      (node (ref "U$21") (pin "REXT") (pinfunction "REXT_REXT") (pintype "bidirectional"))
    )
    (net (code "107") (name "VCC") (class "Default")
      (node (ref "JP1") (pin "2") (pinfunction "2_2") (pintype "passive"))
      (node (ref "R1") (pin "1") (pinfunction "1_1") (pintype "passive"))
      (node (ref "R10") (pin "1") (pinfunction "1_1") (pintype "passive"))
      (node (ref "R11") (pin "1") (pinfunction "1_1") (pintype "passive"))
      (node (ref "R12") (pin "1") (pinfunction "1_1") (pintype "passive"))
      (node (ref "R13") (pin "1") (pinfunction "1_1") (pintype "passive"))
      (node (ref "R14") (pin "1") (pinfunction "1_1") (pintype "passive"))
      (node (ref "R15") (pin "1") (pinfunction "1_1") (pintype "passive"))
      (node (ref "R16") (pin "1") (pinfunction "1_1") (pintype "passive"))
      (node (ref "R17") (pin "1") (pinfunction "1_1") (pintype "passive"))
      (node (ref "R18") (pin "1") (pinfunction "1_1") (pintype "passive"))
      (node (ref "R19") (pin "1") (pinfunction "1_1") (pintype "passive"))
      (node (ref "R2") (pin "1") (pinfunction "1_1") (pintype "passive"))
      (node (ref "R20") (pin "1") (pinfunction "1_1") (pintype "passive"))
      (node (ref "R21") (pin "1") (pinfunction "1_1") (pintype "passive"))
      (node (ref "R3") (pin "1") (pinfunction "1_1") (pintype "passive"))
      (node (ref "R4") (pin "1") (pinfunction "1_1") (pintype "passive"))
      (node (ref "R5") (pin "1") (pinfunction "1_1") (pintype "passive"))
      (node (ref "R6") (pin "1") (pinfunction "1_1") (pintype "passive"))
      (node (ref "R7") (pin "1") (pinfunction "1_1") (pintype "passive"))
      (node (ref "R8") (pin "1") (pinfunction "1_1") (pintype "passive"))
      (node (ref "R9") (pin "1") (pinfunction "1_1") (pintype "passive"))
      (node (ref "U$1") (pin "VSS") (pinfunction "VSS_VSS") (pintype "bidirectional"))
      (node (ref "U$10") (pin "VSS") (pinfunction "VSS_VSS") (pintype "bidirectional"))
      (node (ref "U$11") (pin "VSS") (pinfunction "VSS_VSS") (pintype "bidirectional"))
      (node (ref "U$12") (pin "VSS") (pinfunction "VSS_VSS") (pintype "bidirectional"))
      (node (ref "U$13") (pin "VSS") (pinfunction "VSS_VSS") (pintype "bidirectional"))
      (node (ref "U$14") (pin "VSS") (pinfunction "VSS_VSS") (pintype "bidirectional"))
      (node (ref "U$15") (pin "VSS") (pinfunction "VSS_VSS") (pintype "bidirectional"))
      (node (ref "U$16") (pin "VSS") (pinfunction "VSS_VSS") (pintype "bidirectional"))
      (node (ref "U$17") (pin "VSS") (pinfunction "VSS_VSS") (pintype "bidirectional"))
      (node (ref "U$18") (pin "VSS") (pinfunction "VSS_VSS") (pintype "bidirectional"))
      (node (ref "U$19") (pin "VSS") (pinfunction "VSS_VSS") (pintype "bidirectional"))
      (node (ref "U$2") (pin "VSS") (pinfunction "VSS_VSS") (pintype "bidirectional"))
      (node (ref "U$20") (pin "VSS") (pinfunction "VSS_VSS") (pintype "bidirectional"))
      (node (ref "U$21") (pin "VSS") (pinfunction "VSS_VSS") (pintype "bidirectional"))
      (node (ref "U$3") (pin "VSS") (pinfunction "VSS_VSS") (pintype "bidirectional"))
      (node (ref "U$4") (pin "VSS") (pinfunction "VSS_VSS") (pintype "bidirectional"))
      (node (ref "U$5") (pin "VSS") (pinfunction "VSS_VSS") (pintype "bidirectional"))
      (node (ref "U$6") (pin "VSS") (pinfunction "VSS_VSS") (pintype "bidirectional"))
      (node (ref "U$7") (pin "VSS") (pinfunction "VSS_VSS") (pintype "bidirectional"))
      (node (ref "U$8") (pin "VSS") (pinfunction "VSS_VSS") (pintype "bidirectional"))
      (node (ref "U$9") (pin "VSS") (pinfunction "VSS_VSS") (pintype "bidirectional"))
    )
  )
)
